# Smartfin_Main_PCBA_USB.net
KiCad netlist of a schematic drawn in Altium Designer
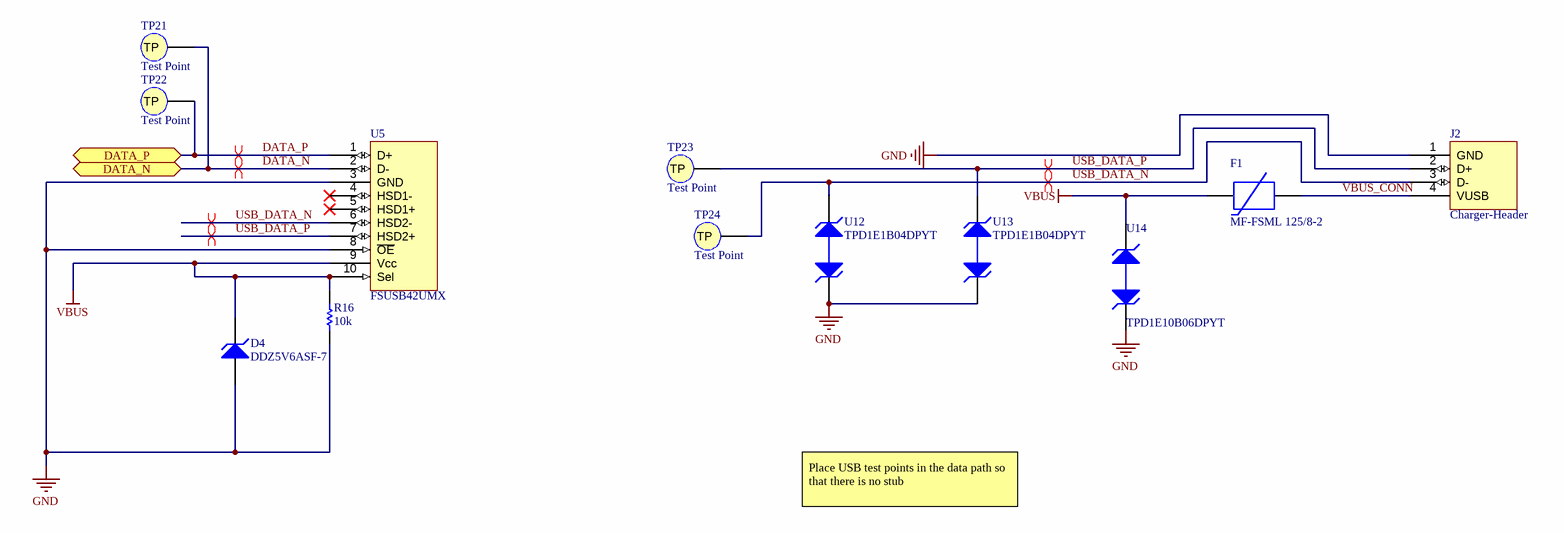
[diagram p0: Smartfin Main PCBA USB.SchDoc]

(export (version "E")
  (design (tool "Eeschema 10.0.6"))
  (components
    (comp (ref "D4")
      (value "DDZ5V6ASF-7")
      (footprint "SOD323F")
      (description "DIODE ZENER 5.42V 200MW SOD-323")
      (fields (field (name "TOLERANCE") "±3%") (field (name "MANUFACTURER") "Diodes Inc."))
      (libsource (lib "Syncroness Vault") (part "Zener Diode"))
    )
    (comp (ref "F1")
      (value "MF-FSML 125/8-2")
      (footprint "MF-FSMF010X-2-Footprint-1")
      (description "0603 SMD POLYMER PTC 1.25A/8V")
      (fields (field (name "MANUFACTURER") "Bourns"))
      (libsource (lib "Syncroness Vault") (part "MF-FSML 125/8-2"))
    )
    (comp (ref "J2")
      (value "Charger-Header")
      (footprint "New footprint 1")
      (description "usb power connection")
      (libsource (lib "Syncroness Vault") (part "New symbol 1"))
    )
    (comp (ref "R16")
      (value "10k")
      (footprint "RESC0402(1005)_N")
      (description "RES SMD 10K OHM 0.1% 1/16W 0402")
      (fields
        (field (name "TOLERANCE") "±0.1%")
        (field (name "MANUFACTURER") "Panasonic Electronic Components")
      )
      (libsource (lib "Syncroness Vault") (part "RES"))
    )
    (comp (ref "TP21")
      (value "Test Point")
      (footprint "TESTPAD_ICT")
      (description "ICT Test Point")
      (libsource (lib "Syncroness Vault") (part "TestPointPadOnly"))
    )
    (comp (ref "TP22")
      (value "Test Point")
      (footprint "TESTPAD_ICT")
      (description "ICT Test Point")
      (libsource (lib "Syncroness Vault") (part "TestPointPadOnly"))
    )
    (comp (ref "TP23")
      (value "Test Point")
      (footprint "TESTPAD_ICT")
      (description "ICT Test Point")
      (libsource (lib "Syncroness Vault") (part "TestPointPadOnly"))
    )
    (comp (ref "TP24")
      (value "Test Point")
      (footprint "TESTPAD_ICT")
      (description "ICT Test Point")
      (libsource (lib "Syncroness Vault") (part "TestPointPadOnly"))
    )
    (comp (ref "U5")
      (value "FSUSB42UMX")
      (footprint "FSUSB42UMX-Footprint-1")
      (description "USB MULTIMEDIA SWITCHES")
      (fields (field (name "MANUFACTURER") "On Semiconductor"))
      (libsource (lib "Syncroness Vault") (part "FSUSB42UMX"))
    )
    (comp (ref "U12")
      (value "TPD1E1B04DPYT")
      (footprint "TPD1E10B06DPYT-Footprint-1")
      (description "TVS DIODE 3.6V 8.5V 2X1SON")
      (fields (field (name "MANUFACTURER") "Texas Instruments"))
      (libsource (lib "") (part "TPD1E10B06DPYR_1"))
    )
    (comp (ref "U13")
      (value "TPD1E1B04DPYT")
      (footprint "TPD1E10B06DPYT-Footprint-1")
      (description "TVS DIODE 3.6V 8.5V 2X1SON")
      (fields (field (name "MANUFACTURER") "Texas Instruments"))
      (libsource (lib "") (part "TPD1E10B06DPYR_1"))
    )
    (comp (ref "U14")
      (value "TPD1E10B06DPYT")
      (footprint "TPD1E10B06DPYT-Footprint-1")
      (description "TVS DIODE 5.5VWM 14VC 2X2SON")
      (fields (field (name "MANUFACTURER") "Texas Instruments"))
      (libsource (lib "Syncroness Vault") (part "TPD1E10B06DPYR"))
    )
  )
  (nets
    (net (code "1") (name "/DATA_N") (class "Default")
      (node (ref "TP21") (pin "1") (pinfunction "TP_1") (pintype "passive"))
      (node (ref "U5") (pin "2") (pinfunction "D-_2") (pintype "bidirectional"))
    )
    (net (code "2") (name "/DATA_P") (class "Default")
      (node (ref "TP22") (pin "1") (pinfunction "TP_1") (pintype "passive"))
      (node (ref "U5") (pin "1") (pinfunction "D+_1") (pintype "bidirectional"))
    )
    (net (code "3") (name "/USB_DATA_N") (class "Default")
      (node (ref "J2") (pin "3") (pinfunction "D-_3") (pintype "bidirectional"))
      (node (ref "TP24") (pin "1") (pinfunction "TP_1") (pintype "passive"))
      (node (ref "U12") (pin "2") (pinfunction "2_2") (pintype "passive"))
      (node (ref "U5") (pin "6") (pinfunction "HSD2-_6") (pintype "bidirectional"))
    )
    (net (code "4") (name "/USB_DATA_P") (class "Default")
      (node (ref "J2") (pin "2") (pinfunction "D+_2") (pintype "bidirectional"))
      (node (ref "TP23") (pin "1") (pinfunction "TP_1") (pintype "passive"))
      (node (ref "U13") (pin "1") (pinfunction "1_1") (pintype "passive"))
      (node (ref "U5") (pin "7") (pinfunction "HSD2+_7") (pintype "bidirectional"))
    )
    (net (code "5") (name "/VBUS_CONN") (class "Default")
      (node (ref "F1") (pin "1") (pinfunction "1_1") (pintype "passive"))
      (node (ref "J2") (pin "4") (pinfunction "VUSB_4") (pintype "power_in"))
    )
    (net (code "6") (name "GND") (class "Default")
      (node (ref "D4") (pin "A") (pinfunction "A_A") (pintype "passive"))
      (node (ref "J2") (pin "1") (pinfunction "GND_1") (pintype "power_in"))
      (node (ref "R16") (pin "1") (pinfunction "1_1") (pintype "passive"))
      (node (ref "U12") (pin "1") (pinfunction "1_1") (pintype "passive"))
      (node (ref "U13") (pin "2") (pinfunction "2_2") (pintype "passive"))
      (node (ref "U14") (pin "2") (pinfunction "2_2") (pintype "passive"))
      (node (ref "U5") (pin "3") (pinfunction "GND_3") (pintype "power_in"))
      (node (ref "U5") (pin "8") (pinfunction "~{OE}_8") (pintype "input"))
    )
    (net (code "7") (name "VBUS") (class "Default")
      (node (ref "D4") (pin "K") (pinfunction "K_K") (pintype "passive"))
      (node (ref "F1") (pin "2") (pinfunction "2_2") (pintype "passive"))
      (node (ref "R16") (pin "2") (pinfunction "2_2") (pintype "passive"))
      (node (ref "U14") (pin "1") (pinfunction "1_1") (pintype "passive"))
      (node (ref "U5") (pin "10") (pinfunction "Sel_10") (pintype "input"))
      (node (ref "U5") (pin "9") (pinfunction "Vcc_9") (pintype "power_in"))
    )
    (net (code "8") (name "unconnected-(U5-HSD1+-Pad5)") (class "Default")
      (node (ref "U5") (pin "5") (pinfunction "HSD1+_5") (pintype "bidirectional+no_connect"))
    )
    (net (code "9") (name "unconnected-(U5-HSD1--Pad4)") (class "Default")
      (node (ref "U5") (pin "4") (pinfunction "HSD1-_4") (pintype "bidirectional+no_connect"))
    )
  )
)
